# Sensor11.net
KiCad netlist of a schematic drawn in Altium Designer
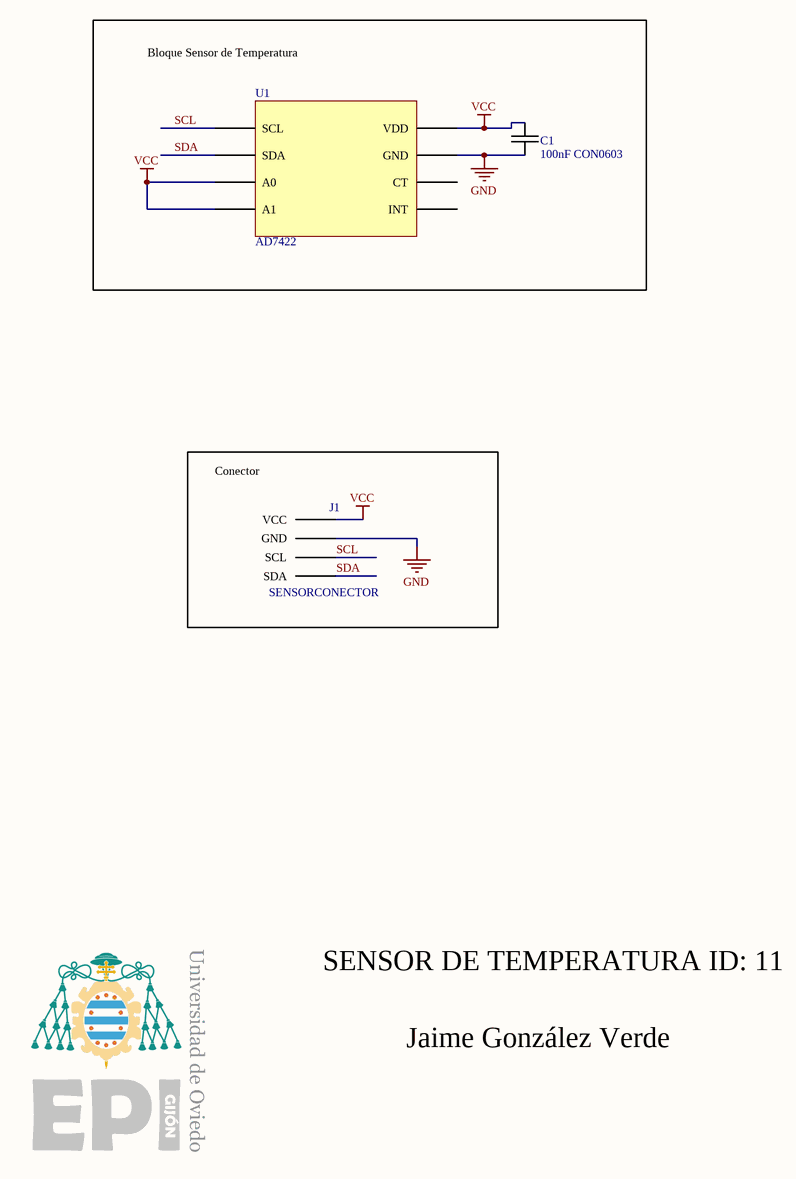
[diagram p0: Sensor11.SchDoc]

(export (version "E")
  (design (tool "Eeschema 10.0.6"))
  (components
    (comp (ref "C1")
      (value "100nF CON0603")
      (footprint "CAPC0603X06N")
      (libsource (lib "JaimeGlez") (part "CON0603"))
    )
    (comp (ref "J1")
      (value "SENSORCONECTOR")
      (footprint "ConectorSMD1,3mm")
      (libsource (lib "JaimeGlez") (part "SENSORCONECTOR"))
    )
    (comp (ref "U1") (value "AD7422") (footprint "ADT7422") (libsource (lib "JaimeGlez") (part "AD7422")))
  )
  (nets
    (net (code "1") (name "/SCL") (class "Default")
      (node (ref "J1") (pin "1") (pinfunction "SCL_1") (pintype "passive"))
      (node (ref "U1") (pin "1") (pinfunction "SCL_1") (pintype "passive"))
    )
    (net (code "2") (name "/SDA") (class "Default")
      (node (ref "J1") (pin "0") (pinfunction "SDA_0") (pintype "passive"))
      (node (ref "U1") (pin "2") (pinfunction "SDA_2") (pintype "passive"))
    )
    (net (code "3") (name "GND") (class "Default")
      (node (ref "C1") (pin "1") (pintype "passive"))
      (node (ref "J1") (pin "2") (pinfunction "GND_2") (pintype "passive"))
      (node (ref "U1") (pin "11") (pinfunction "GND_11") (pintype "passive"))
    )
    (net (code "4") (name "VCC") (class "Default")
      (node (ref "C1") (pin "2") (pintype "passive"))
      (node (ref "J1") (pin "3") (pinfunction "VCC_3") (pintype "passive"))
      (node (ref "U1") (pin "12") (pinfunction "VDD_12") (pintype "passive"))
      (node (ref "U1") (pin "3") (pinfunction "A0_3") (pintype "passive"))
      (node (ref "U1") (pin "4") (pinfunction "A1_4") (pintype "passive"))
    )
    (net (code "5") (name "unconnected-(U1-CT-Pad10)") (class "Default")
      (node (ref "U1") (pin "10") (pinfunction "CT_10") (pintype "passive"))
    )
    (net (code "6") (name "unconnected-(U1-INT-Pad9)") (class "Default")
      (node (ref "U1") (pin "9") (pinfunction "INT_9") (pintype "passive"))
    )
  )
)
